# 05_LMS7002M_Misc.net
KiCad netlist of a schematic drawn in Altium Designer
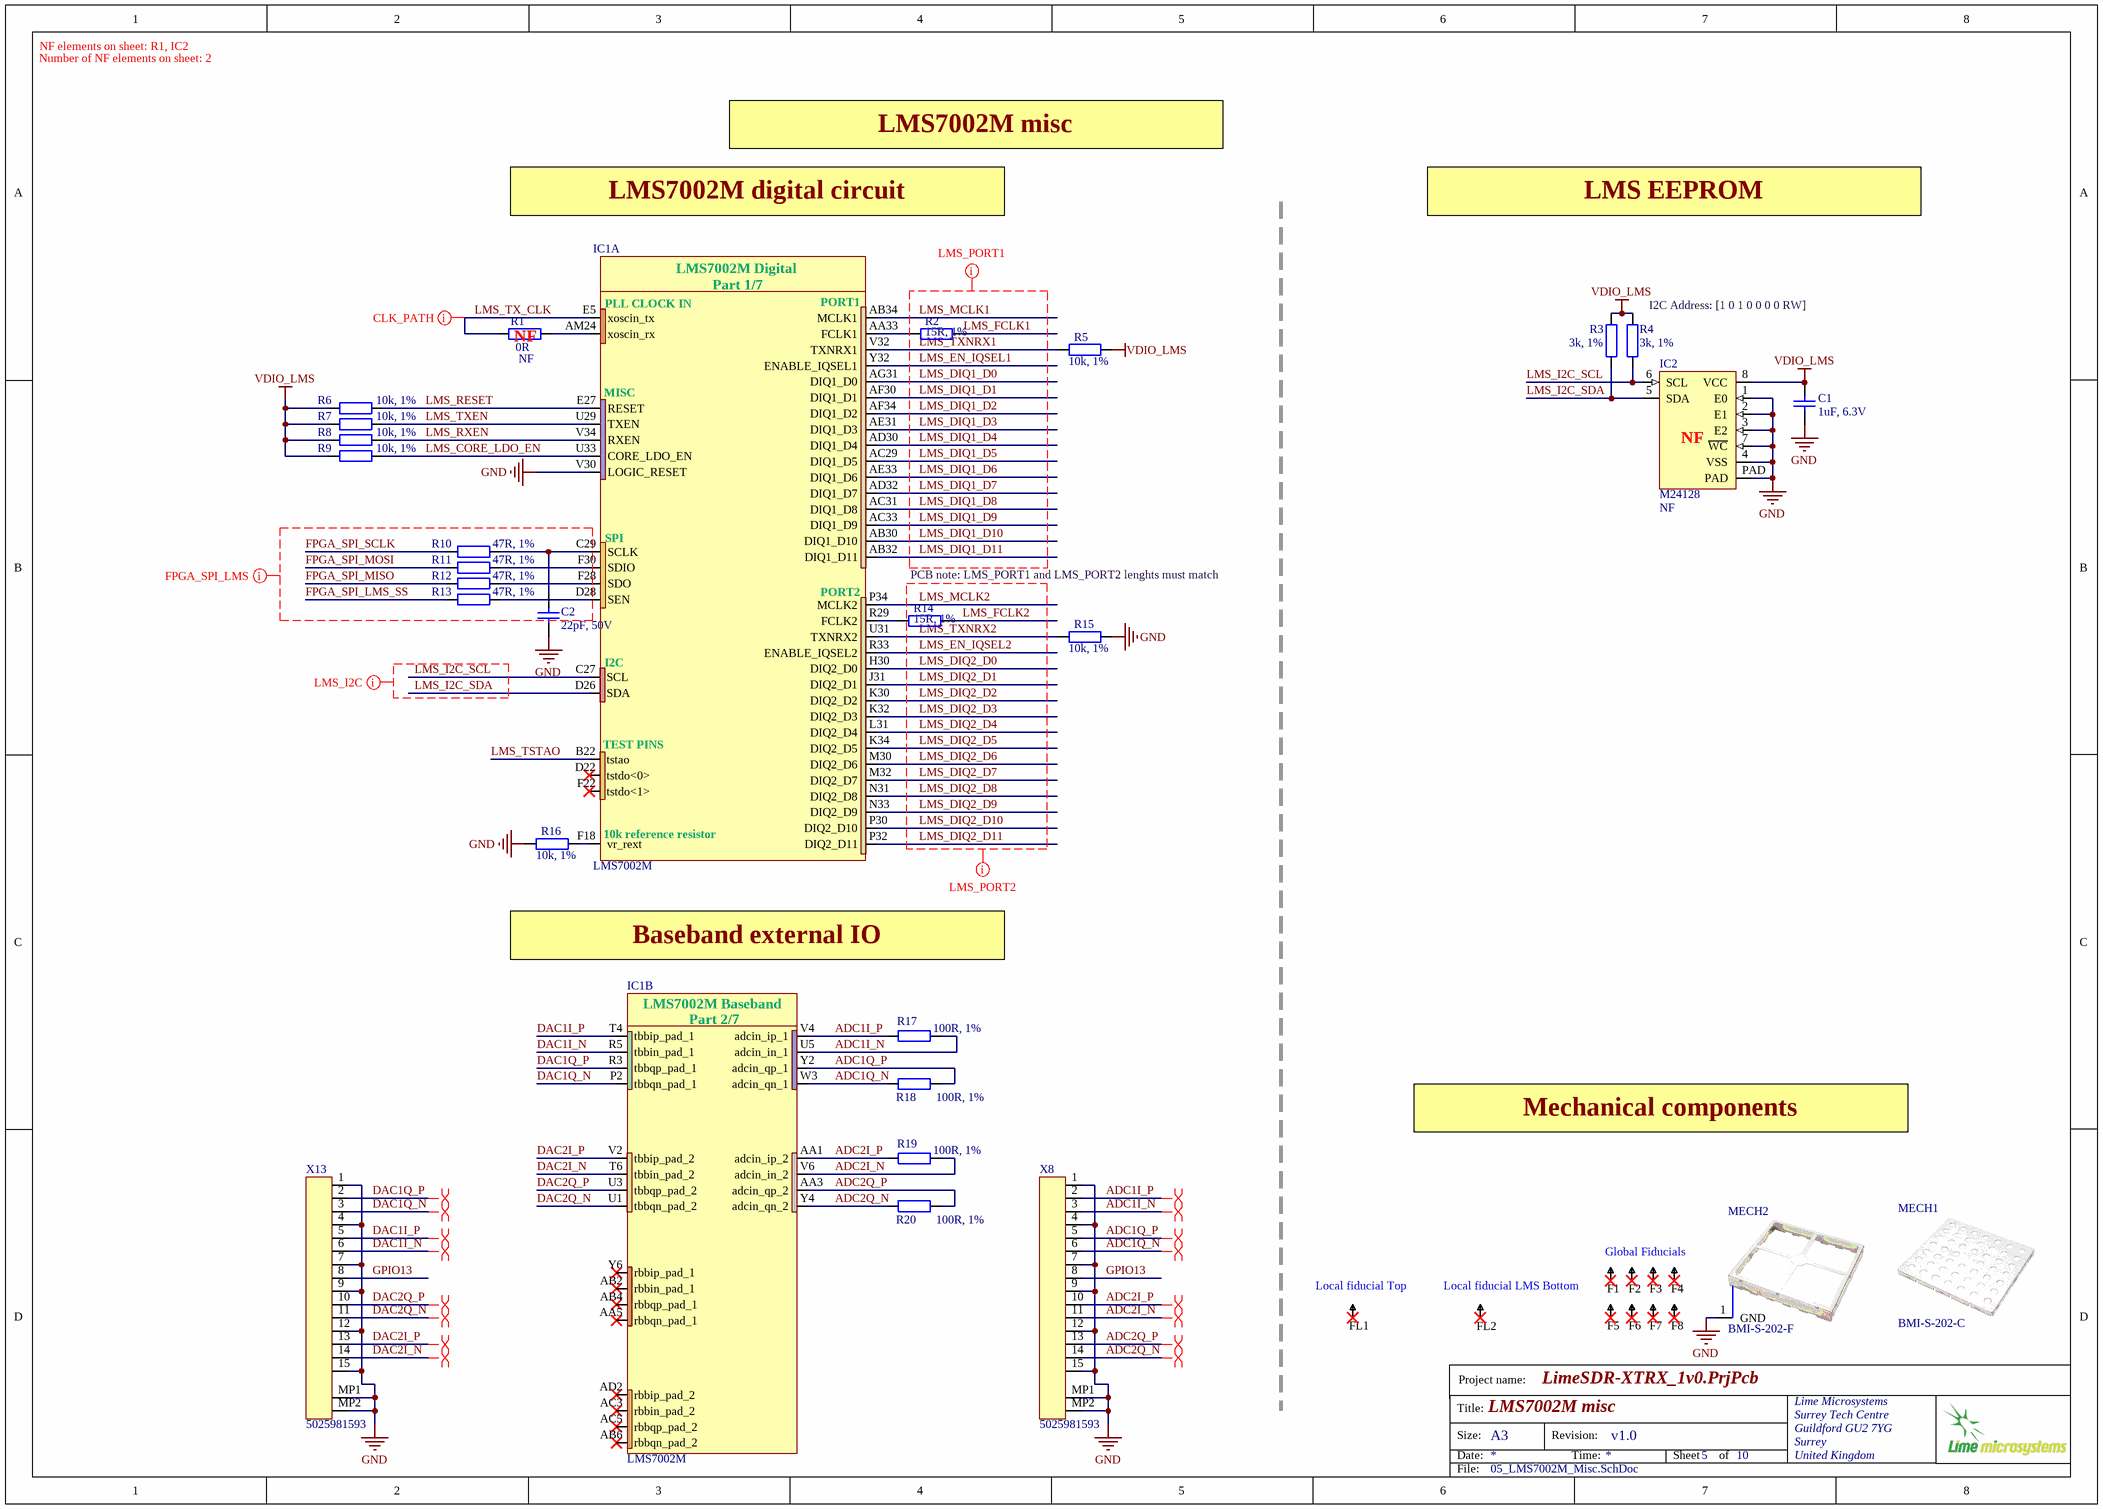
[diagram p0: 05_LMS7002M_Misc.SchDoc]

(export (version "E")
  (design (tool "Eeschema 10.0.6"))
  (components
    (comp (ref "C1")
      (value "1uF, 6.3V")
      (footprint "CAP0201")
      (fields (field (name "TOLERANCE") "±20%") (field (name "MANUFACTURER") "TDK Corporation"))
      (libsource (lib "LimeMicroAltiumLib_schLib") (part "Cap_0402"))
    )
    (comp (ref "C2")
      (value "22pF, 50V")
      (footprint "CAP0201")
      (fields
        (field (name "MANUFACTURER") "Murata")
        (field (name "TOLERANCE") "5%")
        (field (name "VOLTAGE") "50V")
      )
      (libsource (lib "LimeMicroAltiumLib_schLib") (part "Cap_0402"))
    )
    (comp (ref "F1")
      (value "Fiducial")
      (footprint "Fiducial")
      (libsource (lib "VGTU_Altium_lib") (part "Fiducial"))
    )
    (comp (ref "F2")
      (value "Fiducial")
      (footprint "Fiducial")
      (libsource (lib "VGTU_Altium_lib") (part "Fiducial"))
    )
    (comp (ref "F3")
      (value "Fiducial")
      (footprint "Fiducial")
      (libsource (lib "VGTU_Altium_lib") (part "Fiducial"))
    )
    (comp (ref "F4")
      (value "Fiducial")
      (footprint "Fiducial")
      (libsource (lib "VGTU_Altium_lib") (part "Fiducial"))
    )
    (comp (ref "F5")
      (value "Fiducial")
      (footprint "Fiducial")
      (libsource (lib "VGTU_Altium_lib") (part "Fiducial"))
    )
    (comp (ref "F6")
      (value "Fiducial")
      (footprint "Fiducial")
      (libsource (lib "VGTU_Altium_lib") (part "Fiducial"))
    )
    (comp (ref "F7")
      (value "Fiducial")
      (footprint "Fiducial")
      (libsource (lib "VGTU_Altium_lib") (part "Fiducial"))
    )
    (comp (ref "F8")
      (value "Fiducial")
      (footprint "Fiducial")
      (libsource (lib "VGTU_Altium_lib") (part "Fiducial"))
    )
    (comp (ref "FL1")
      (value "Fiducial")
      (footprint "Fiducial_local")
      (libsource (lib "") (part "Fiducial_1"))
    )
    (comp (ref "FL2")
      (value "Fiducial")
      (footprint "Fiducial_local")
      (libsource (lib "") (part "Fiducial_1"))
    )
    (comp (ref "IC1")
      (value "LMS7002M")
      (footprint "LMS7002M_v5_LESS_SILK")
      (description "Schematic symbol revision 4. Default footprint - 0.31mm pad")
      (fields (field (name "MANUFACTURER") "Lime Microsystems"))
      (libsource (lib "LimeMicroAltiumLib_schLib_r04") (part "LMS7002Mr4"))
    )
    (comp (ref "IC2")
      (value "M24128")
      (footprint "M24128-DFMC6TG")
      (fields (field (name "MANUFACTURER") "STMicroelectronics") (field (name "ASSEMBLY INFO") "NF"))
      (libsource (lib "LimeMicroAltiumLib_schLib") (part "M24128-DFMC6TG"))
    )
    (comp (ref "MECH1")
      (value "BMI-S-202-C")
      (footprint "BMI-S-202-C_RF_SHIELD_COVER")
      (fields (field (name "MANUFACTURER") "Laird"))
      (libsource (lib "LimeMicroAltiumLib_schLib_r04") (part "RFI_SHIELD_COVER_BMI-S-202-C"))
    )
    (comp (ref "MECH2")
      (value "BMI-S-202-F")
      (footprint "BMI-S-202-F_RF_SHIELD_FRAME_v2")
      (fields (field (name "MANUFACTURER") "Laird"))
      (libsource (lib "LimeMicroAltiumLib_schLib_r04") (part "RFI_SHIELD_FRAME_BMI-S-202-F"))
    )
    (comp (ref "R1")
      (value "0R")
      (footprint "RES0201")
      (fields
        (field (name "ASSEMBLY INFO") "NF")
        (field (name "MANUFACTURER") "Yageo")
        (field (name "TOLERANCE") "5%")
      )
      (libsource (lib "LimeFPGAboard_schLib") (part "Res_0402"))
    )
    (comp (ref "R2")
      (value "15R, 1%")
      (footprint "RES0201")
      (fields (field (name "MANUFACTURER") "Yageo") (field (name "TOLERANCE") "1%"))
      (libsource (lib "LimeFPGAboard_schLib") (part "Res_0402"))
    )
    (comp (ref "R3")
      (value "3k, 1%")
      (footprint "RES0201")
      (fields (field (name "MANUFACTURER") "Yageo") (field (name "TOLERANCE") "1%"))
      (libsource (lib "LimeFPGAboard_schLib") (part "Res_0402"))
    )
    (comp (ref "R4")
      (value "3k, 1%")
      (footprint "RES0201")
      (fields (field (name "MANUFACTURER") "Yageo") (field (name "TOLERANCE") "1%"))
      (libsource (lib "LimeFPGAboard_schLib") (part "Res_0402"))
    )
    (comp (ref "R5")
      (value "10k, 1%")
      (footprint "RES0201")
      (fields (field (name "MANUFACTURER") "Yageo") (field (name "TOLERANCE") "1%"))
      (libsource (lib "LimeFPGAboard_schLib") (part "Res_0402"))
    )
    (comp (ref "R6")
      (value "10k, 1%")
      (footprint "RES0201")
      (fields (field (name "MANUFACTURER") "Yageo") (field (name "TOLERANCE") "1%"))
      (libsource (lib "LimeFPGAboard_schLib") (part "Res_0402"))
    )
    (comp (ref "R7")
      (value "10k, 1%")
      (footprint "RES0201")
      (fields (field (name "MANUFACTURER") "Yageo") (field (name "TOLERANCE") "1%"))
      (libsource (lib "LimeFPGAboard_schLib") (part "Res_0402"))
    )
    (comp (ref "R8")
      (value "10k, 1%")
      (footprint "RES0201")
      (fields (field (name "MANUFACTURER") "Yageo") (field (name "TOLERANCE") "1%"))
      (libsource (lib "LimeFPGAboard_schLib") (part "Res_0402"))
    )
    (comp (ref "R9")
      (value "10k, 1%")
      (footprint "RES0201")
      (fields (field (name "MANUFACTURER") "Yageo") (field (name "TOLERANCE") "1%"))
      (libsource (lib "LimeFPGAboard_schLib") (part "Res_0402"))
    )
    (comp (ref "R10")
      (value "47R, 1%")
      (footprint "RES0201")
      (fields (field (name "MANUFACTURER") "Yageo") (field (name "TOLERANCE") "1%"))
      (libsource (lib "LimeFPGAboard_schLib") (part "Res_0402"))
    )
    (comp (ref "R11")
      (value "47R, 1%")
      (footprint "RES0201")
      (fields (field (name "MANUFACTURER") "Yageo") (field (name "TOLERANCE") "1%"))
      (libsource (lib "LimeFPGAboard_schLib") (part "Res_0402"))
    )
    (comp (ref "R12")
      (value "47R, 1%")
      (footprint "RES0201")
      (fields (field (name "MANUFACTURER") "Yageo") (field (name "TOLERANCE") "1%"))
      (libsource (lib "LimeFPGAboard_schLib") (part "Res_0402"))
    )
    (comp (ref "R13")
      (value "47R, 1%")
      (footprint "RES0201")
      (fields (field (name "MANUFACTURER") "Yageo") (field (name "TOLERANCE") "1%"))
      (libsource (lib "LimeFPGAboard_schLib") (part "Res_0402"))
    )
    (comp (ref "R14")
      (value "15R, 1%")
      (footprint "RES0201")
      (fields (field (name "MANUFACTURER") "Yageo") (field (name "TOLERANCE") "1%"))
      (libsource (lib "LimeFPGAboard_schLib") (part "Res_0402"))
    )
    (comp (ref "R15")
      (value "10k, 1%")
      (footprint "RES0201")
      (fields (field (name "MANUFACTURER") "Yageo") (field (name "TOLERANCE") "1%"))
      (libsource (lib "LimeFPGAboard_schLib") (part "Res_0402"))
    )
    (comp (ref "R16")
      (value "10k, 1%")
      (footprint "RES0201")
      (fields (field (name "MANUFACTURER") "Yageo") (field (name "TOLERANCE") "1%"))
      (libsource (lib "LimeFPGAboard_schLib") (part "Res_0402"))
    )
    (comp (ref "R17")
      (value "100R, 1%")
      (footprint "RES0201")
      (fields (field (name "MANUFACTURER") "Yageo") (field (name "TOLERANCE") "1%"))
      (libsource (lib "LimeFPGAboard_schLib") (part "Res_0402"))
    )
    (comp (ref "R18")
      (value "100R, 1%")
      (footprint "RES0201")
      (fields (field (name "MANUFACTURER") "Yageo") (field (name "TOLERANCE") "1%"))
      (libsource (lib "LimeFPGAboard_schLib") (part "Res_0402"))
    )
    (comp (ref "R19")
      (value "100R, 1%")
      (footprint "RES0201")
      (fields (field (name "MANUFACTURER") "Yageo") (field (name "TOLERANCE") "1%"))
      (libsource (lib "LimeFPGAboard_schLib") (part "Res_0402"))
    )
    (comp (ref "R20")
      (value "100R, 1%")
      (footprint "RES0201")
      (fields (field (name "MANUFACTURER") "Yageo") (field (name "TOLERANCE") "1%"))
      (libsource (lib "LimeFPGAboard_schLib") (part "Res_0402"))
    )
    (comp (ref "X8")
      (value "5025981593")
      (footprint "5025981593_FPC_connector")
      (fields (field (name "MANUFACTURER") "Molex"))
      (libsource (lib "LimeMicroAltiumLib_schLib_r04") (part "5025981593_FPC_connector"))
    )
    (comp (ref "X13")
      (value "5025981593")
      (footprint "5025981593_FPC_connector")
      (fields (field (name "MANUFACTURER") "Molex"))
      (libsource (lib "LimeMicroAltiumLib_schLib_r04") (part "5025981593_FPC_connector"))
    )
  )
  (nets
    (net (code "1") (name "/ADC1I_N") (class "Default")
      (node (ref "IC1") (pin "U5") (pinfunction "adcin_in_1_U5") (pintype "passive"))
      (node (ref "R17") (pin "2") (pinfunction "2_2") (pintype "passive"))
      (node (ref "X8") (pin "3") (pinfunction "3_3") (pintype "passive"))
    )
    (net (code "2") (name "/ADC1I_P") (class "Default")
      (node (ref "IC1") (pin "V4") (pinfunction "adcin_ip_1_V4") (pintype "passive"))
      (node (ref "R17") (pin "1") (pinfunction "1_1") (pintype "passive"))
      (node (ref "X8") (pin "2") (pinfunction "2_2") (pintype "passive"))
    )
    (net (code "3") (name "/ADC1Q_N") (class "Default")
      (node (ref "IC1") (pin "W3") (pinfunction "adcin_qn_1_W3") (pintype "passive"))
      (node (ref "R18") (pin "1") (pinfunction "1_1") (pintype "passive"))
      (node (ref "X8") (pin "6") (pinfunction "6_6") (pintype "passive"))
    )
    (net (code "4") (name "/ADC1Q_P") (class "Default")
      (node (ref "IC1") (pin "Y2") (pinfunction "adcin_qp_1_Y2") (pintype "passive"))
      (node (ref "R18") (pin "2") (pinfunction "2_2") (pintype "passive"))
      (node (ref "X8") (pin "5") (pinfunction "5_5") (pintype "passive"))
    )
    (net (code "5") (name "/ADC2I_N") (class "Default")
      (node (ref "IC1") (pin "V6") (pinfunction "adcin_in_2_V6") (pintype "passive"))
      (node (ref "R19") (pin "2") (pinfunction "2_2") (pintype "passive"))
      (node (ref "X8") (pin "11") (pinfunction "11_11") (pintype "passive"))
    )
    (net (code "6") (name "/ADC2I_P") (class "Default")
      (node (ref "IC1") (pin "AA1") (pinfunction "adcin_ip_2_AA1") (pintype "passive"))
      (node (ref "R19") (pin "1") (pinfunction "1_1") (pintype "passive"))
      (node (ref "X8") (pin "10") (pinfunction "10_10") (pintype "passive"))
    )
    (net (code "7") (name "/ADC2Q_N") (class "Default")
      (node (ref "IC1") (pin "Y4") (pinfunction "adcin_qn_2_Y4") (pintype "passive"))
      (node (ref "R20") (pin "1") (pinfunction "1_1") (pintype "passive"))
      (node (ref "X8") (pin "14") (pinfunction "14_14") (pintype "passive"))
    )
    (net (code "8") (name "/ADC2Q_P") (class "Default")
      (node (ref "IC1") (pin "AA3") (pinfunction "adcin_qp_2_AA3") (pintype "passive"))
      (node (ref "R20") (pin "2") (pinfunction "2_2") (pintype "passive"))
      (node (ref "X8") (pin "13") (pinfunction "13_13") (pintype "passive"))
    )
    (net (code "9") (name "/DAC1I_N") (class "Default")
      (node (ref "IC1") (pin "R5") (pinfunction "tbbin_pad_1_R5") (pintype "passive"))
      (node (ref "X13") (pin "6") (pinfunction "6_6") (pintype "passive"))
    )
    (net (code "10") (name "/DAC1I_P") (class "Default")
      (node (ref "IC1") (pin "T4") (pinfunction "tbbip_pad_1_T4") (pintype "passive"))
      (node (ref "X13") (pin "5") (pinfunction "5_5") (pintype "passive"))
    )
    (net (code "11") (name "/DAC1Q_N") (class "Default")
      (node (ref "IC1") (pin "P2") (pinfunction "tbbqn_pad_1_P2") (pintype "passive"))
      (node (ref "X13") (pin "3") (pinfunction "3_3") (pintype "passive"))
    )
    (net (code "12") (name "/DAC1Q_P") (class "Default")
      (node (ref "IC1") (pin "R3") (pinfunction "tbbqp_pad_1_R3") (pintype "passive"))
      (node (ref "X13") (pin "2") (pinfunction "2_2") (pintype "passive"))
    )
    (net (code "13") (name "/DAC2I_N") (class "Default")
      (node (ref "IC1") (pin "T6") (pinfunction "tbbin_pad_2_T6") (pintype "passive"))
      (node (ref "X13") (pin "14") (pinfunction "14_14") (pintype "passive"))
    )
    (net (code "14") (name "/DAC2I_P") (class "Default")
      (node (ref "IC1") (pin "V2") (pinfunction "tbbip_pad_2_V2") (pintype "passive"))
      (node (ref "X13") (pin "13") (pinfunction "13_13") (pintype "passive"))
    )
    (net (code "15") (name "/DAC2Q_N") (class "Default")
      (node (ref "IC1") (pin "U1") (pinfunction "tbbqn_pad_2_U1") (pintype "passive"))
      (node (ref "X13") (pin "11") (pinfunction "11_11") (pintype "passive"))
    )
    (net (code "16") (name "/DAC2Q_P") (class "Default")
      (node (ref "IC1") (pin "U3") (pinfunction "tbbqp_pad_2_U3") (pintype "passive"))
      (node (ref "X13") (pin "10") (pinfunction "10_10") (pintype "passive"))
    )
    (net (code "17") (name "/FPGA_SPI_LMS_SS") (class "Default")
      (node (ref "R13") (pin "2") (pinfunction "2_2") (pintype "passive"))
    )
    (net (code "18") (name "/FPGA_SPI_MISO") (class "Default")
      (node (ref "R12") (pin "2") (pinfunction "2_2") (pintype "passive"))
    )
    (net (code "19") (name "/FPGA_SPI_MOSI") (class "Default")
      (node (ref "R11") (pin "2") (pinfunction "2_2") (pintype "passive"))
    )
    (net (code "20") (name "/FPGA_SPI_SCLK") (class "Default")
      (node (ref "R10") (pin "2") (pinfunction "2_2") (pintype "passive"))
    )
    (net (code "21") (name "/GPIO13") (class "Default")
      (node (ref "X13") (pin "8") (pinfunction "8_8") (pintype "passive"))
      (node (ref "X8") (pin "8") (pinfunction "8_8") (pintype "passive"))
    )
    (net (code "22") (name "/LMS_CORE_LDO_EN") (class "Default")
      (node (ref "IC1") (pin "U33") (pinfunction "CORE_LDO_EN_U33") (pintype "passive"))
      (node (ref "R9") (pin "1") (pinfunction "1_1") (pintype "passive"))
    )
    (net (code "23") (name "/LMS_DIQ1_D0") (class "Default")
      (node (ref "IC1") (pin "AG31") (pinfunction "DIQ1_D0_AG31") (pintype "passive"))
    )
    (net (code "24") (name "/LMS_DIQ1_D1") (class "Default")
      (node (ref "IC1") (pin "AF30") (pinfunction "DIQ1_D1_AF30") (pintype "passive"))
    )
    (net (code "25") (name "/LMS_DIQ1_D2") (class "Default")
      (node (ref "IC1") (pin "AF34") (pinfunction "DIQ1_D2_AF34") (pintype "passive"))
    )
    (net (code "26") (name "/LMS_DIQ1_D3") (class "Default")
      (node (ref "IC1") (pin "AE31") (pinfunction "DIQ1_D3_AE31") (pintype "passive"))
    )
    (net (code "27") (name "/LMS_DIQ1_D4") (class "Default")
      (node (ref "IC1") (pin "AD30") (pinfunction "DIQ1_D4_AD30") (pintype "passive"))
    )
    (net (code "28") (name "/LMS_DIQ1_D5") (class "Default")
      (node (ref "IC1") (pin "AC29") (pinfunction "DIQ1_D5_AC29") (pintype "passive"))
    )
    (net (code "29") (name "/LMS_DIQ1_D6") (class "Default")
      (node (ref "IC1") (pin "AE33") (pinfunction "DIQ1_D6_AE33") (pintype "passive"))
    )
    (net (code "30") (name "/LMS_DIQ1_D7") (class "Default")
      (node (ref "IC1") (pin "AD32") (pinfunction "DIQ1_D7_AD32") (pintype "passive"))
    )
    (net (code "31") (name "/LMS_DIQ1_D8") (class "Default")
      (node (ref "IC1") (pin "AC31") (pinfunction "DIQ1_D8_AC31") (pintype "passive"))
    )
    (net (code "32") (name "/LMS_DIQ1_D9") (class "Default")
      (node (ref "IC1") (pin "AC33") (pinfunction "DIQ1_D9_AC33") (pintype "passive"))
    )
    (net (code "33") (name "/LMS_DIQ1_D10") (class "Default")
      (node (ref "IC1") (pin "AB30") (pinfunction "DIQ1_D10_AB30") (pintype "passive"))
    )
    (net (code "34") (name "/LMS_DIQ1_D11") (class "Default")
      (node (ref "IC1") (pin "AB32") (pinfunction "DIQ1_D11_AB32") (pintype "passive"))
    )
    (net (code "35") (name "/LMS_DIQ2_D0") (class "Default")
      (node (ref "IC1") (pin "H30") (pinfunction "DIQ2_D0_H30") (pintype "passive"))
    )
    (net (code "36") (name "/LMS_DIQ2_D1") (class "Default")
      (node (ref "IC1") (pin "J31") (pinfunction "DIQ2_D1_J31") (pintype "passive"))
    )
    (net (code "37") (name "/LMS_DIQ2_D2") (class "Default")
      (node (ref "IC1") (pin "K30") (pinfunction "DIQ2_D2_K30") (pintype "passive"))
    )
    (net (code "38") (name "/LMS_DIQ2_D3") (class "Default")
      (node (ref "IC1") (pin "K32") (pinfunction "DIQ2_D3_K32") (pintype "passive"))
    )
    (net (code "39") (name "/LMS_DIQ2_D4") (class "Default")
      (node (ref "IC1") (pin "L31") (pinfunction "DIQ2_D4_L31") (pintype "passive"))
    )
    (net (code "40") (name "/LMS_DIQ2_D5") (class "Default")
      (node (ref "IC1") (pin "K34") (pinfunction "DIQ2_D5_K34") (pintype "passive"))
    )
    (net (code "41") (name "/LMS_DIQ2_D6") (class "Default")
      (node (ref "IC1") (pin "M30") (pinfunction "DIQ2_D6_M30") (pintype "passive"))
    )
    (net (code "42") (name "/LMS_DIQ2_D7") (class "Default")
      (node (ref "IC1") (pin "M32") (pinfunction "DIQ2_D7_M32") (pintype "passive"))
    )
    (net (code "43") (name "/LMS_DIQ2_D8") (class "Default")
      (node (ref "IC1") (pin "N31") (pinfunction "DIQ2_D8_N31") (pintype "passive"))
    )
    (net (code "44") (name "/LMS_DIQ2_D9") (class "Default")
      (node (ref "IC1") (pin "N33") (pinfunction "DIQ2_D9_N33") (pintype "passive"))
    )
    (net (code "45") (name "/LMS_DIQ2_D10") (class "Default")
      (node (ref "IC1") (pin "P30") (pinfunction "DIQ2_D10_P30") (pintype "passive"))
    )
    (net (code "46") (name "/LMS_DIQ2_D11") (class "Default")
      (node (ref "IC1") (pin "P32") (pinfunction "DIQ2_D11_P32") (pintype "passive"))
    )
    (net (code "47") (name "/LMS_EN_IQSEL1") (class "Default")
      (node (ref "IC1") (pin "Y32") (pinfunction "ENABLE_IQSEL1_Y32") (pintype "passive"))
    )
    (net (code "48") (name "/LMS_EN_IQSEL2") (class "Default")
      (node (ref "IC1") (pin "R33") (pinfunction "ENABLE_IQSEL2_R33") (pintype "passive"))
    )
    (net (code "49") (name "/LMS_FCLK1") (class "Default")
      (node (ref "R2") (pin "1") (pinfunction "1_1") (pintype "passive"))
    )
    (net (code "50") (name "/LMS_FCLK2") (class "Default")
      (node (ref "R14") (pin "1") (pinfunction "1_1") (pintype "passive"))
    )
    (net (code "51") (name "/LMS_I2C_SCL") (class "Default")
      (node (ref "IC1") (pin "C27") (pinfunction "SCL_C27") (pintype "passive"))
      (node (ref "IC2") (pin "6") (pinfunction "SCL_6") (pintype "input"))
      (node (ref "R4") (pin "1") (pinfunction "1_1") (pintype "passive"))
    )
    (net (code "52") (name "/LMS_I2C_SDA") (class "Default")
      (node (ref "IC1") (pin "D26") (pinfunction "SDA_D26") (pintype "passive"))
      (node (ref "IC2") (pin "5") (pinfunction "SDA_5") (pintype "bidirectional"))
      (node (ref "R3") (pin "1") (pinfunction "1_1") (pintype "passive"))
    )
    (net (code "53") (name "/LMS_MCLK1") (class "Default")
      (node (ref "IC1") (pin "AB34") (pinfunction "MCLK1_AB34") (pintype "passive"))
    )
    (net (code "54") (name "/LMS_MCLK2") (class "Default")
      (node (ref "IC1") (pin "P34") (pinfunction "MCLK2_P34") (pintype "passive"))
    )
    (net (code "55") (name "/LMS_RESET") (class "Default")
      (node (ref "IC1") (pin "E27") (pinfunction "RESET_E27") (pintype "passive"))
      (node (ref "R6") (pin "1") (pinfunction "1_1") (pintype "passive"))
    )
    (net (code "56") (name "/LMS_RXEN") (class "Default")
      (node (ref "IC1") (pin "V34") (pinfunction "RXEN_V34") (pintype "passive"))
      (node (ref "R8") (pin "1") (pinfunction "1_1") (pintype "passive"))
    )
    (net (code "57") (name "/LMS_TSTAO") (class "Default")
      (node (ref "IC1") (pin "B22") (pinfunction "tstao_B22") (pintype "passive"))
    )
    (net (code "58") (name "/LMS_TXEN") (class "Default")
      (node (ref "IC1") (pin "U29") (pinfunction "TXEN_U29") (pintype "passive"))
      (node (ref "R7") (pin "1") (pinfunction "1_1") (pintype "passive"))
    )
    (net (code "59") (name "/LMS_TXNRX1") (class "Default")
      (node (ref "IC1") (pin "V32") (pinfunction "TXNRX1_V32") (pintype "passive"))
      (node (ref "R5") (pin "2") (pinfunction "2_2") (pintype "passive"))
    )
    (net (code "60") (name "/LMS_TXNRX2") (class "Default")
      (node (ref "IC1") (pin "U31") (pinfunction "TXNRX2_U31") (pintype "passive"))
      (node (ref "R15") (pin "2") (pinfunction "2_2") (pintype "passive"))
    )
    (net (code "61") (name "/LMS_TX_CLK") (class "Default")
      (node (ref "IC1") (pin "E5") (pinfunction "xoscin_tx_E5") (pintype "passive"))
      (node (ref "R1") (pin "1") (pinfunction "1_1") (pintype "passive"))
    )
    (net (code "62") (name "GND") (class "Default")
      (node (ref "C1") (pin "2") (pinfunction "2_2") (pintype "passive"))
      (node (ref "C2") (pin "1") (pinfunction "1_1") (pintype "passive"))
      (node (ref "IC1") (pin "V30") (pinfunction "LOGIC_RESET_V30") (pintype "passive"))
      (node (ref "IC2") (pin "1") (pinfunction "E0_1") (pintype "input"))
      (node (ref "IC2") (pin "2") (pinfunction "E1_2") (pintype "input"))
      (node (ref "IC2") (pin "3") (pinfunction "E2_3") (pintype "input"))
      (node (ref "IC2") (pin "4") (pinfunction "VSS_4") (pintype "power_in"))
      (node (ref "IC2") (pin "7") (pinfunction "~{WC}_7") (pintype "input"))
      (node (ref "IC2") (pin "PAD") (pinfunction "PAD_PAD") (pintype "power_in"))
      (node (ref "MECH2") (pin "1") (pinfunction "GND_1") (pintype "passive"))
      (node (ref "R15") (pin "1") (pinfunction "1_1") (pintype "passive"))
      (node (ref "R16") (pin "2") (pinfunction "2_2") (pintype "passive"))
      (node (ref "X13") (pin "1") (pinfunction "1_1") (pintype "passive"))
      (node (ref "X13") (pin "12") (pinfunction "12_12") (pintype "passive"))
      (node (ref "X13") (pin "15") (pinfunction "15_15") (pintype "passive"))
      (node (ref "X13") (pin "4") (pinfunction "4_4") (pintype "passive"))
      (node (ref "X13") (pin "7") (pinfunction "7_7") (pintype "passive"))
      (node (ref "X13") (pin "9") (pinfunction "9_9") (pintype "passive"))
      (node (ref "X13") (pin "MP1") (pinfunction "MP1_MP1") (pintype "passive"))
      (node (ref "X13") (pin "MP2") (pinfunction "MP2_MP2") (pintype "passive"))
      (node (ref "X8") (pin "1") (pinfunction "1_1") (pintype "passive"))
      (node (ref "X8") (pin "12") (pinfunction "12_12") (pintype "passive"))
      (node (ref "X8") (pin "15") (pinfunction "15_15") (pintype "passive"))
      (node (ref "X8") (pin "4") (pinfunction "4_4") (pintype "passive"))
      (node (ref "X8") (pin "7") (pinfunction "7_7") (pintype "passive"))
      (node (ref "X8") (pin "9") (pinfunction "9_9") (pintype "passive"))
      (node (ref "X8") (pin "MP1") (pinfunction "MP1_MP1") (pintype "passive"))
      (node (ref "X8") (pin "MP2") (pinfunction "MP2_MP2") (pintype "passive"))
    )
    (net (code "63") (name "Net-(IC1A-FCLK1)") (class "Default")
      (node (ref "IC1") (pin "AA33") (pinfunction "FCLK1_AA33") (pintype "passive"))
      (node (ref "R2") (pin "2") (pinfunction "2_2") (pintype "passive"))
    )
    (net (code "64") (name "Net-(IC1A-FCLK2)") (class "Default")
      (node (ref "IC1") (pin "R29") (pinfunction "FCLK2_R29") (pintype "passive"))
      (node (ref "R14") (pin "2") (pinfunction "2_2") (pintype "passive"))
    )
    (net (code "65") (name "Net-(IC1A-SCLK)") (class "Default")
      (node (ref "C2") (pin "2") (pinfunction "2_2") (pintype "passive"))
      (node (ref "IC1") (pin "C29") (pinfunction "SCLK_C29") (pintype "passive"))
      (node (ref "R10") (pin "1") (pinfunction "1_1") (pintype "passive"))
    )
    (net (code "66") (name "Net-(IC1A-SDIO)") (class "Default")
      (node (ref "IC1") (pin "F30") (pinfunction "SDIO_F30") (pintype "passive"))
      (node (ref "R11") (pin "1") (pinfunction "1_1") (pintype "passive"))
    )
    (net (code "67") (name "Net-(IC1A-SDO)") (class "Default")
      (node (ref "IC1") (pin "F28") (pinfunction "SDO_F28") (pintype "passive"))
      (node (ref "R12") (pin "1") (pinfunction "1_1") (pintype "passive"))
    )
    (net (code "68") (name "Net-(IC1A-SEN)") (class "Default")
      (node (ref "IC1") (pin "D28") (pinfunction "SEN_D28") (pintype "passive"))
      (node (ref "R13") (pin "1") (pinfunction "1_1") (pintype "passive"))
    )
    (net (code "69") (name "Net-(IC1A-vr_rext)") (class "Default")
      (node (ref "IC1") (pin "F18") (pinfunction "vr_rext_F18") (pintype "passive"))
      (node (ref "R16") (pin "1") (pinfunction "1_1") (pintype "passive"))
    )
    (net (code "70") (name "Net-(IC1A-xoscin_rx)") (class "Default")
      (node (ref "IC1") (pin "AM24") (pinfunction "xoscin_rx_AM24") (pintype "passive"))
      (node (ref "R1") (pin "2") (pinfunction "2_2") (pintype "passive"))
    )
    (net (code "71") (name "VDIO_LMS") (class "Default")
      (node (ref "C1") (pin "1") (pinfunction "1_1") (pintype "passive"))
      (node (ref "IC2") (pin "8") (pinfunction "VCC_8") (pintype "power_in"))
      (node (ref "R3") (pin "2") (pinfunction "2_2") (pintype "passive"))
      (node (ref "R4") (pin "2") (pinfunction "2_2") (pintype "passive"))
      (node (ref "R5") (pin "1") (pinfunction "1_1") (pintype "passive"))
      (node (ref "R6") (pin "2") (pinfunction "2_2") (pintype "passive"))
      (node (ref "R7") (pin "2") (pinfunction "2_2") (pintype "passive"))
      (node (ref "R8") (pin "2") (pinfunction "2_2") (pintype "passive"))
      (node (ref "R9") (pin "2") (pinfunction "2_2") (pintype "passive"))
    )
    (net (code "72") (name "unconnected-(F1-Pad1)") (class "Default")
      (node (ref "F1") (pin "1") (pintype "passive+no_connect"))
    )
    (net (code "73") (name "unconnected-(F2-Pad1)") (class "Default")
      (node (ref "F2") (pin "1") (pintype "passive+no_connect"))
    )
    (net (code "74") (name "unconnected-(F3-Pad1)") (class "Default")
      (node (ref "F3") (pin "1") (pintype "passive+no_connect"))
    )
    (net (code "75") (name "unconnected-(F4-Pad1)") (class "Default")
      (node (ref "F4") (pin "1") (pintype "passive+no_connect"))
    )
    (net (code "76") (name "unconnected-(F5-Pad1)") (class "Default")
      (node (ref "F5") (pin "1") (pintype "passive+no_connect"))
    )
    (net (code "77") (name "unconnected-(F6-Pad1)") (class "Default")
      (node (ref "F6") (pin "1") (pintype "passive+no_connect"))
    )
    (net (code "78") (name "unconnected-(F7-Pad1)") (class "Default")
      (node (ref "F7") (pin "1") (pintype "passive+no_connect"))
    )
    (net (code "79") (name "unconnected-(F8-Pad1)") (class "Default")
      (node (ref "F8") (pin "1") (pintype "passive+no_connect"))
    )
    (net (code "80") (name "unconnected-(FL1-Pad1)") (class "Default")
      (node (ref "FL1") (pin "1") (pintype "passive+no_connect"))
    )
    (net (code "81") (name "unconnected-(FL2-Pad1)") (class "Default")
      (node (ref "FL2") (pin "1") (pintype "passive+no_connect"))
    )
    (net (code "82") (name "unconnected-(IC1A-tstdo<0>-PadD22)") (class "Default")
      (node (ref "IC1") (pin "D22") (pinfunction "tstdo<0>_D22") (pintype "passive+no_connect"))
    )
    (net (code "83") (name "unconnected-(IC1A-tstdo<1>-PadF22)") (class "Default")
      (node (ref "IC1") (pin "F22") (pinfunction "tstdo<1>_F22") (pintype "passive+no_connect"))
    )
    (net (code "84") (name "unconnected-(IC1B-rbbin_pad_1-PadAB2)") (class "Default")
      (node (ref "IC1") (pin "AB2") (pinfunction "rbbin_pad_1_AB2") (pintype "passive+no_connect"))
    )
    (net (code "85") (name "unconnected-(IC1B-rbbin_pad_2-PadAC3)") (class "Default")
      (node (ref "IC1") (pin "AC3") (pinfunction "rbbin_pad_2_AC3") (pintype "passive+no_connect"))
    )
    (net (code "86") (name "unconnected-(IC1B-rbbip_pad_1-PadY6)") (class "Default")
      (node (ref "IC1") (pin "Y6") (pinfunction "rbbip_pad_1_Y6") (pintype "passive+no_connect"))
    )
    (net (code "87") (name "unconnected-(IC1B-rbbip_pad_2-PadAD2)") (class "Default")
      (node (ref "IC1") (pin "AD2") (pinfunction "rbbip_pad_2_AD2") (pintype "passive+no_connect"))
    )
    (net (code "88") (name "unconnected-(IC1B-rbbqn_pad_1-PadAA5)") (class "Default")
      (node (ref "IC1") (pin "AA5") (pinfunction "rbbqn_pad_1_AA5") (pintype "passive+no_connect"))
    )
    (net (code "89") (name "unconnected-(IC1B-rbbqn_pad_2-PadAB6)") (class "Default")
      (node (ref "IC1") (pin "AB6") (pinfunction "rbbqn_pad_2_AB6") (pintype "passive+no_connect"))
    )
    (net (code "90") (name "unconnected-(IC1B-rbbqp_pad_1-PadAB4)") (class "Default")
      (node (ref "IC1") (pin "AB4") (pinfunction "rbbqp_pad_1_AB4") (pintype "passive+no_connect"))
    )
    (net (code "91") (name "unconnected-(IC1B-rbbqp_pad_2-PadAC5)") (class "Default")
      (node (ref "IC1") (pin "AC5") (pinfunction "rbbqp_pad_2_AC5") (pintype "passive+no_connect"))
    )
  )
)
